# Supply-DC3V3.net
KiCad netlist of a schematic drawn in Altium Designer
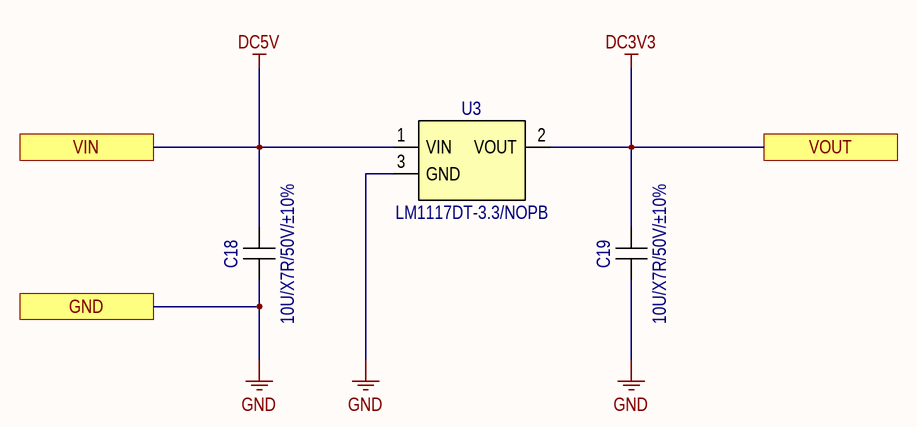
[diagram p0: Supply-DC3V3.SchDoc]

(export (version "E")
  (design (tool "Eeschema 10.0.6"))
  (components
    (comp (ref "C18")
      (value "10U/X7R/50V/±10%")
      (footprint "Normal_Capacitor_Standard_1206-L3200-W1600-BW1250-H1600")
      (description "Ceramic Capacitor SMD 1210")
      (fields (field (name "Comment") "CL31B106KBHNNNE"))
      (libsource (lib "Samsung-MLCC-1206") (part "CL31B106KBHNNNE"))
    )
    (comp (ref "C19")
      (value "10U/X7R/50V/±10%")
      (footprint "Normal_Capacitor_Standard_1206-L3200-W1600-BW1250-H1600")
      (description "Ceramic Capacitor SMD 1210")
      (fields (field (name "Comment") "CL31B106KBHNNNE"))
      (libsource (lib "Samsung-MLCC-1206") (part "CL31B106KBHNNNE"))
    )
    (comp (ref "U3")
      (value "LM1117DT-3.3/NOPB")
      (footprint "SOT223")
      (libsource (lib "mfmc_components") (part "LM1117DT-3.3/NOPB"))
    )
  )
  (nets
    (net (code "1") (name "DC3V3") (class "Default")
      (node (ref "C19") (pin "2") (pintype "passive"))
      (node (ref "U3") (pin "2") (pinfunction "VOUT_2") (pintype "power_in"))
    )
    (net (code "2") (name "DC5V") (class "Default")
      (node (ref "C18") (pin "2") (pintype "passive"))
      (node (ref "U3") (pin "1") (pinfunction "VIN_1") (pintype "power_in"))
    )
    (net (code "3") (name "GND") (class "Default")
      (node (ref "C18") (pin "1") (pintype "passive"))
      (node (ref "C19") (pin "1") (pintype "passive"))
      (node (ref "U3") (pin "3") (pinfunction "GND_3") (pintype "power_in"))
    )
  )
)
